# Xduino6_0.net
KiCad netlist of a schematic drawn in EAGLE
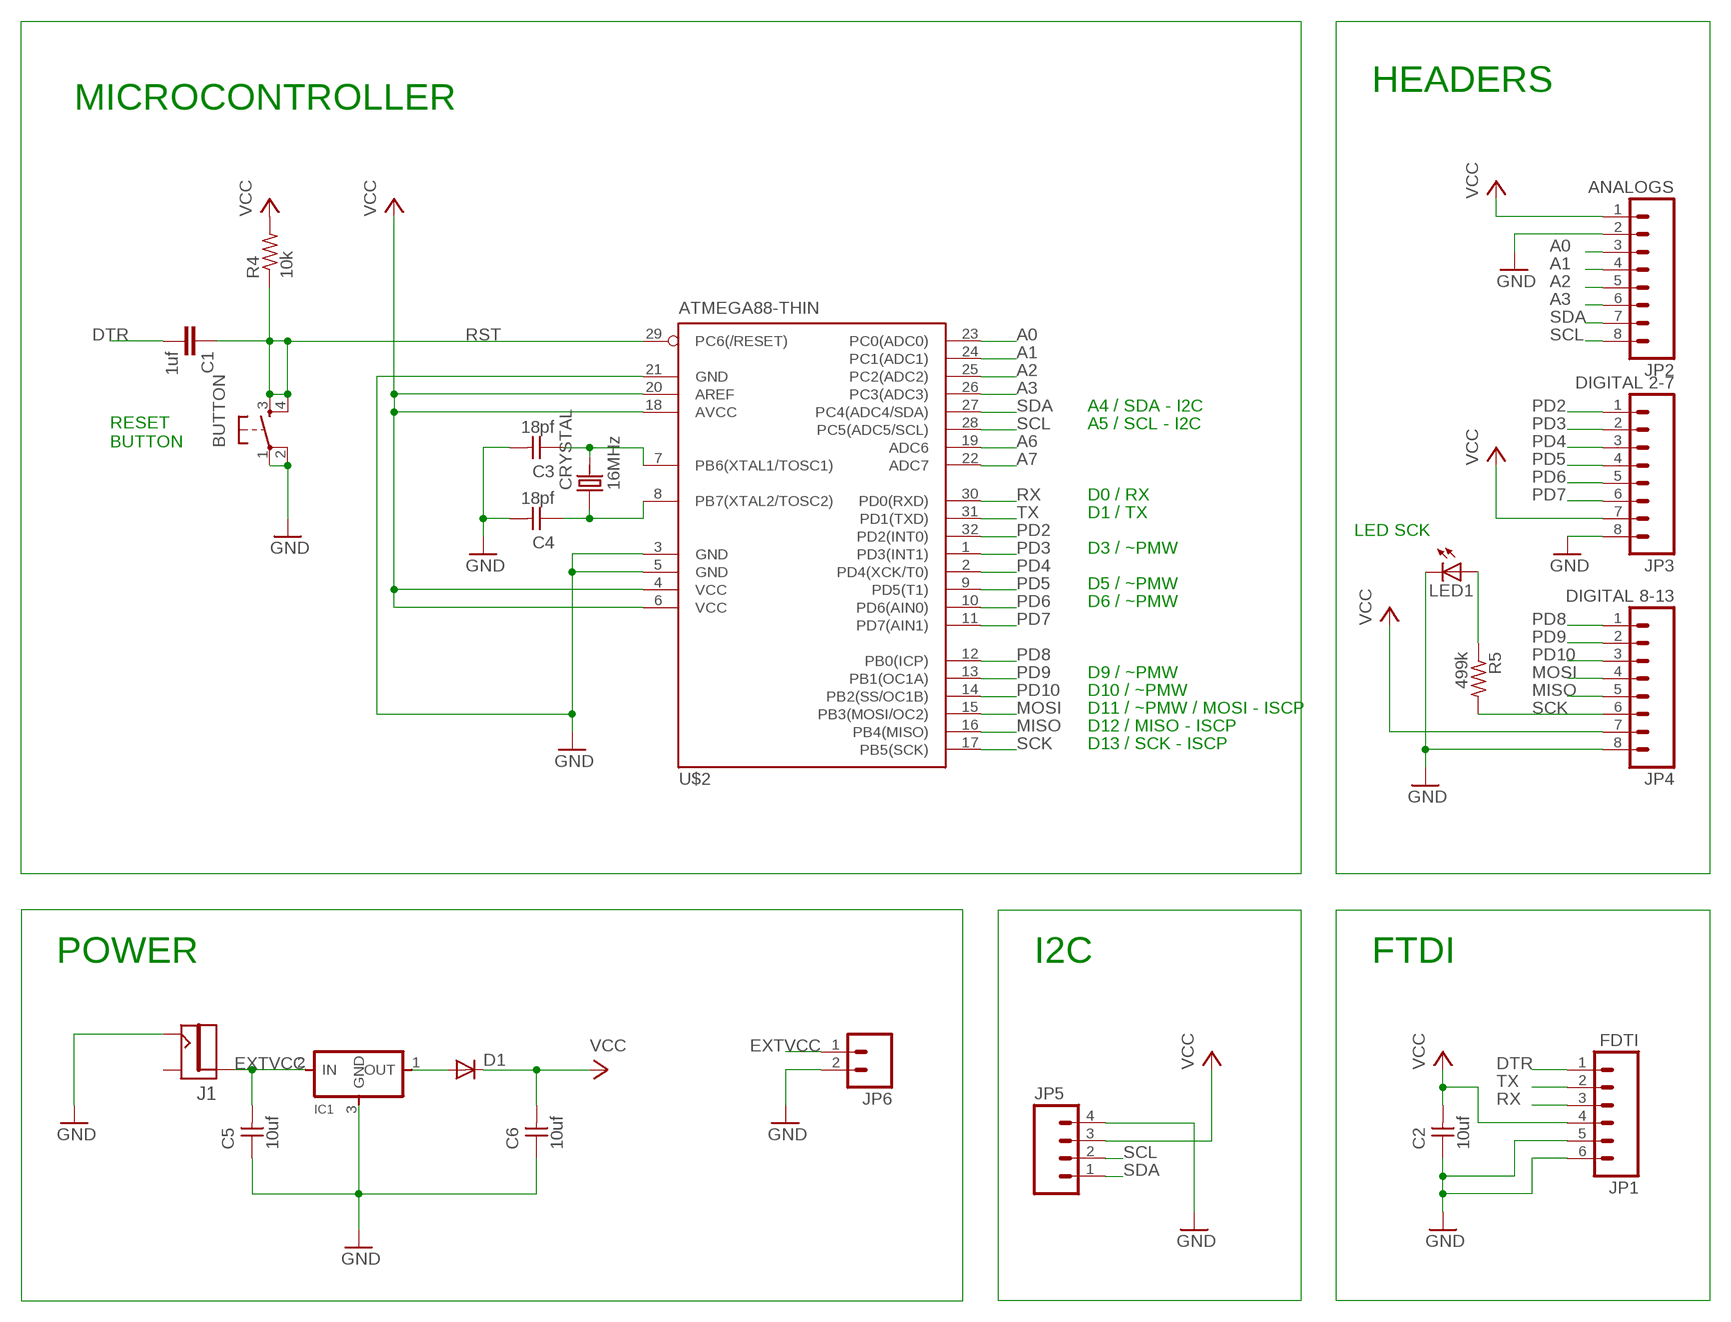
[diagram p0: schematic, sheet 1]

(export (version "E")
  (design (tool "Eeschema 10.0.6"))
  (components
    (comp (ref "BUTTON")
      (value "6MM_SWITCH6MM_SWITCH")
      (footprint "eagle-import:6MM_SWITCH")
      (libsource (lib "eagle-import") (part "6MM_SWITCH6MM_SWITCH"))
    )
    (comp (ref "C1")
      (value "1uf")
      (footprint "eagle-import:1206")
      (libsource (lib "eagle-import") (part "CAP1206"))
    )
    (comp (ref "C2")
      (value "10uf")
      (footprint "eagle-import:1206")
      (libsource (lib "eagle-import") (part "UNPOLARIZED_CAPACITOR1206"))
    )
    (comp (ref "C3")
      (value "18pf")
      (footprint "eagle-import:1206")
      (libsource (lib "eagle-import") (part "UNPOLARIZED_CAPACITOR1206"))
    )
    (comp (ref "C4")
      (value "18pf")
      (footprint "eagle-import:1206")
      (libsource (lib "eagle-import") (part "UNPOLARIZED_CAPACITOR1206"))
    )
    (comp (ref "C5")
      (value "10uf")
      (footprint "eagle-import:1206")
      (libsource (lib "eagle-import") (part "UNPOLARIZED_CAPACITOR1206"))
    )
    (comp (ref "C6")
      (value "10uf")
      (footprint "eagle-import:1206")
      (libsource (lib "eagle-import") (part "UNPOLARIZED_CAPACITOR1206"))
    )
    (comp (ref "CRYSTAL")
      (value "16MHz")
      (footprint "eagle-import:CS10")
      (libsource (lib "eagle-import") (part "CRYSTALCS10"))
    )
    (comp (ref "D1")
      (value "DIODESOD123")
      (footprint "eagle-import:SOD123")
      (libsource (lib "eagle-import") (part "DIODESOD123"))
    )
    (comp (ref "IC1")
      (value "REGULATORSOT23")
      (footprint "eagle-import:SOT23")
      (libsource (lib "eagle-import") (part "REGULATORSOT23"))
    )
    (comp (ref "J1")
      (value "JACK.65MM")
      (footprint "eagle-import:JACK_.65MM")
      (libsource (lib "eagle-import") (part "JACK.65MM"))
    )
    (comp (ref "JP1")
      (value "FDTI")
      (footprint "eagle-import:1X06-SMD_EDGE")
      (libsource (lib "eagle-import") (part "M061X06-SMD_EDGE_FEMALE"))
    )
    (comp (ref "JP2")
      (value "ANALOGS")
      (footprint "eagle-import:1X08")
      (libsource (lib "eagle-import") (part "M08"))
    )
    (comp (ref "JP3")
      (value "DIGITAL 2-7")
      (footprint "eagle-import:1X08")
      (libsource (lib "eagle-import") (part "M08"))
    )
    (comp (ref "JP4")
      (value "DIGITAL 8-13")
      (footprint "eagle-import:1X08")
      (libsource (lib "eagle-import") (part "M08"))
    )
    (comp (ref "JP5")
      (value "M04PTH")
      (footprint "eagle-import:1X04")
      (libsource (lib "eagle-import") (part "M04PTH"))
    )
    (comp (ref "JP6")
      (value "M02PTH")
      (footprint "eagle-import:1X02")
      (libsource (lib "eagle-import") (part "M02PTH"))
    )
    (comp (ref "LED1")
      (value "LED1206")
      (footprint "eagle-import:1206")
      (libsource (lib "eagle-import") (part "LED1206"))
    )
    (comp (ref "R4")
      (value "10k")
      (footprint "eagle-import:1206")
      (libsource (lib "eagle-import") (part "RESISTOR1206"))
    )
    (comp (ref "R5")
      (value "499k")
      (footprint "eagle-import:1206")
      (libsource (lib "eagle-import") (part "01_ng_RESISTOR1206"))
    )
    (comp (ref "U$2")
      (value "ATMEGA88-THIN")
      (footprint "eagle-import:TQFP32-08THIN")
      (libsource (lib "eagle-import") (part "ATMEGA88-THIN"))
    )
  )
  (nets
    (net (code "1") (name "/A0") (class "Default")
      (node (ref "JP2") (pin "3") (pinfunction "3_3") (pintype "passive"))
      (node (ref "U$2") (pin "23") (pinfunction "PC0(ADC0)_23") (pintype "bidirectional"))
    )
    (net (code "2") (name "/A1") (class "Default")
      (node (ref "JP2") (pin "4") (pinfunction "4_4") (pintype "passive"))
      (node (ref "U$2") (pin "24") (pinfunction "PC1(ADC1)_24") (pintype "bidirectional"))
    )
    (net (code "3") (name "/A2") (class "Default")
      (node (ref "JP2") (pin "5") (pinfunction "5_5") (pintype "passive"))
      (node (ref "U$2") (pin "25") (pinfunction "PC2(ADC2)_25") (pintype "bidirectional"))
    )
    (net (code "4") (name "/A3") (class "Default")
      (node (ref "JP2") (pin "6") (pinfunction "6_6") (pintype "passive"))
      (node (ref "U$2") (pin "26") (pinfunction "PC3(ADC3)_26") (pintype "bidirectional"))
    )
    (net (code "5") (name "/A6") (class "Default")
      (node (ref "U$2") (pin "19") (pinfunction "ADC6_19") (pintype "bidirectional"))
    )
    (net (code "6") (name "/A7") (class "Default")
      (node (ref "U$2") (pin "22") (pinfunction "ADC7_22") (pintype "bidirectional"))
    )
    (net (code "7") (name "/DTR") (class "Default")
      (node (ref "C1") (pin "2") (pinfunction "2_2") (pintype "passive"))
      (node (ref "JP1") (pin "1") (pinfunction "1_1") (pintype "passive"))
    )
    (net (code "8") (name "/EXTVCC") (class "Default")
      (node (ref "C5") (pin "2") (pinfunction "2_2") (pintype "passive"))
      (node (ref "IC1") (pin "2") (pinfunction "IN_2") (pintype "bidirectional"))
      (node (ref "J1") (pin "PIN") (pinfunction "PIN_PIN") (pintype "bidirectional"))
      (node (ref "JP6") (pin "1") (pinfunction "1_1") (pintype "passive"))
    )
    (net (code "9") (name "/MISO") (class "Default")
      (node (ref "JP4") (pin "5") (pinfunction "5_5") (pintype "passive"))
      (node (ref "U$2") (pin "16") (pinfunction "PB4(MISO)_16") (pintype "bidirectional"))
    )
    (net (code "10") (name "/MOSI") (class "Default")
      (node (ref "JP4") (pin "4") (pinfunction "4_4") (pintype "passive"))
      (node (ref "U$2") (pin "15") (pinfunction "PB3(MOSI/OC2)_15") (pintype "bidirectional"))
    )
    (net (code "11") (name "/PD2") (class "Default")
      (node (ref "JP3") (pin "1") (pinfunction "1_1") (pintype "passive"))
      (node (ref "U$2") (pin "32") (pinfunction "PD2(INT0)_32") (pintype "bidirectional"))
    )
    (net (code "12") (name "/PD3") (class "Default")
      (node (ref "JP3") (pin "2") (pinfunction "2_2") (pintype "passive"))
      (node (ref "U$2") (pin "1") (pinfunction "PD3(INT1)_1") (pintype "bidirectional"))
    )
    (net (code "13") (name "/PD4") (class "Default")
      (node (ref "JP3") (pin "3") (pinfunction "3_3") (pintype "passive"))
      (node (ref "U$2") (pin "2") (pinfunction "PD4(XCK/T0)_2") (pintype "bidirectional"))
    )
    (net (code "14") (name "/PD5") (class "Default")
      (node (ref "JP3") (pin "4") (pinfunction "4_4") (pintype "passive"))
      (node (ref "U$2") (pin "9") (pinfunction "PD5(T1)_9") (pintype "bidirectional"))
    )
    (net (code "15") (name "/PD6") (class "Default")
      (node (ref "JP3") (pin "5") (pinfunction "5_5") (pintype "passive"))
      (node (ref "U$2") (pin "10") (pinfunction "PD6(AIN0)_10") (pintype "bidirectional"))
    )
    (net (code "16") (name "/PD7") (class "Default")
      (node (ref "JP3") (pin "6") (pinfunction "6_6") (pintype "passive"))
      (node (ref "U$2") (pin "11") (pinfunction "PD7(AIN1)_11") (pintype "bidirectional"))
    )
    (net (code "17") (name "/PD8") (class "Default")
      (node (ref "JP4") (pin "1") (pinfunction "1_1") (pintype "passive"))
      (node (ref "U$2") (pin "12") (pinfunction "PB0(ICP)_12") (pintype "bidirectional"))
    )
    (net (code "18") (name "/PD9") (class "Default")
      (node (ref "JP4") (pin "2") (pinfunction "2_2") (pintype "passive"))
      (node (ref "U$2") (pin "13") (pinfunction "PB1(OC1A)_13") (pintype "bidirectional"))
    )
    (net (code "19") (name "/PD10") (class "Default")
      (node (ref "JP4") (pin "3") (pinfunction "3_3") (pintype "passive"))
      (node (ref "U$2") (pin "14") (pinfunction "PB2(SS/OC1B)_14") (pintype "bidirectional"))
    )
    (net (code "20") (name "/RST") (class "Default")
      (node (ref "BUTTON") (pin "3") (pinfunction "S_3") (pintype "passive"))
      (node (ref "BUTTON") (pin "4") (pinfunction "S1_4") (pintype "passive"))
      (node (ref "C1") (pin "1") (pinfunction "1_1") (pintype "passive"))
      (node (ref "R4") (pin "1") (pinfunction "1_1") (pintype "passive"))
      (node (ref "U$2") (pin "29") (pinfunction "PC6(/RESET)_29") (pintype "bidirectional"))
    )
    (net (code "21") (name "/RX") (class "Default")
      (node (ref "JP1") (pin "3") (pinfunction "3_3") (pintype "passive"))
      (node (ref "U$2") (pin "30") (pinfunction "PD0(RXD)_30") (pintype "bidirectional"))
    )
    (net (code "22") (name "/SCK") (class "Default")
      (node (ref "JP4") (pin "6") (pinfunction "6_6") (pintype "passive"))
      (node (ref "R5") (pin "2") (pinfunction "2_2") (pintype "passive"))
      (node (ref "U$2") (pin "17") (pinfunction "PB5(SCK)_17") (pintype "bidirectional"))
    )
    (net (code "23") (name "/SCL") (class "Default")
      (node (ref "JP2") (pin "8") (pinfunction "8_8") (pintype "passive"))
      (node (ref "JP5") (pin "2") (pinfunction "2_2") (pintype "passive"))
      (node (ref "U$2") (pin "28") (pinfunction "PC5(ADC5/SCL)_28") (pintype "bidirectional"))
    )
    (net (code "24") (name "/SDA") (class "Default")
      (node (ref "JP2") (pin "7") (pinfunction "7_7") (pintype "passive"))
      (node (ref "JP5") (pin "1") (pinfunction "1_1") (pintype "passive"))
      (node (ref "U$2") (pin "27") (pinfunction "PC4(ADC4/SDA)_27") (pintype "bidirectional"))
    )
    (net (code "25") (name "/TX") (class "Default")
      (node (ref "JP1") (pin "2") (pinfunction "2_2") (pintype "passive"))
      (node (ref "U$2") (pin "31") (pinfunction "PD1(TXD)_31") (pintype "bidirectional"))
    )
    (net (code "26") (name "GND") (class "Default")
      (node (ref "BUTTON") (pin "1") (pinfunction "P_1") (pintype "passive"))
      (node (ref "BUTTON") (pin "2") (pinfunction "P1_2") (pintype "passive"))
      (node (ref "C2") (pin "1") (pinfunction "1_1") (pintype "passive"))
      (node (ref "C3") (pin "2") (pinfunction "2_2") (pintype "passive"))
      (node (ref "C4") (pin "2") (pinfunction "2_2") (pintype "passive"))
      (node (ref "C5") (pin "1") (pinfunction "1_1") (pintype "passive"))
      (node (ref "C6") (pin "1") (pinfunction "1_1") (pintype "passive"))
      (node (ref "IC1") (pin "3") (pinfunction "GND_3") (pintype "bidirectional"))
      (node (ref "J1") (pin "SHUNT") (pinfunction "CONTACT_SHUNT") (pintype "bidirectional"))
      (node (ref "JP1") (pin "5") (pinfunction "5_5") (pintype "passive"))
      (node (ref "JP1") (pin "6") (pinfunction "6_6") (pintype "passive"))
      (node (ref "JP2") (pin "2") (pinfunction "2_2") (pintype "passive"))
      (node (ref "JP3") (pin "8") (pinfunction "8_8") (pintype "passive"))
      (node (ref "JP4") (pin "8") (pinfunction "8_8") (pintype "passive"))
      (node (ref "JP5") (pin "4") (pinfunction "4_4") (pintype "passive"))
      (node (ref "JP6") (pin "2") (pinfunction "2_2") (pintype "passive"))
      (node (ref "LED1") (pin "2") (pinfunction "C_2") (pintype "passive"))
      (node (ref "U$2") (pin "21") (pinfunction "GND_21") (pintype "power_in"))
      (node (ref "U$2") (pin "3") (pinfunction "GND_3") (pintype "power_in"))
      (node (ref "U$2") (pin "5") (pinfunction "GND_5") (pintype "power_in"))
    )
    (net (code "27") (name "Net-(CRYSTAL-1)") (class "Default")
      (node (ref "C4") (pin "1") (pinfunction "1_1") (pintype "passive"))
      (node (ref "CRYSTAL") (pin "P$1") (pinfunction "1_P$1") (pintype "passive"))
      (node (ref "U$2") (pin "8") (pinfunction "PB7(XTAL2/TOSC2)_8") (pintype "bidirectional"))
    )
    (net (code "28") (name "Net-(CRYSTAL-2)") (class "Default")
      (node (ref "C3") (pin "1") (pinfunction "1_1") (pintype "passive"))
      (node (ref "CRYSTAL") (pin "P$2") (pinfunction "2_P$2") (pintype "passive"))
      (node (ref "U$2") (pin "7") (pinfunction "PB6(XTAL1/TOSC1)_7") (pintype "bidirectional"))
    )
    (net (code "29") (name "Net-(D1-A)") (class "Default")
      (node (ref "D1") (pin "ANODE") (pinfunction "A_ANODE") (pintype "passive"))
      (node (ref "IC1") (pin "1") (pinfunction "OUT_1") (pintype "bidirectional"))
    )
    (net (code "30") (name "Net-(LED1-A)") (class "Default")
      (node (ref "LED1") (pin "1") (pinfunction "A_1") (pintype "passive"))
      (node (ref "R5") (pin "1") (pinfunction "1_1") (pintype "passive"))
    )
    (net (code "31") (name "VCC") (class "Default")
      (node (ref "C2") (pin "2") (pinfunction "2_2") (pintype "passive"))
      (node (ref "C6") (pin "2") (pinfunction "2_2") (pintype "passive"))
      (node (ref "D1") (pin "CATHODE") (pinfunction "C_CATHODE") (pintype "passive"))
      (node (ref "JP1") (pin "4") (pinfunction "4_4") (pintype "passive"))
      (node (ref "JP2") (pin "1") (pinfunction "1_1") (pintype "passive"))
      (node (ref "JP3") (pin "7") (pinfunction "7_7") (pintype "passive"))
      (node (ref "JP4") (pin "7") (pinfunction "7_7") (pintype "passive"))
      (node (ref "JP5") (pin "3") (pinfunction "3_3") (pintype "passive"))
      (node (ref "R4") (pin "2") (pinfunction "2_2") (pintype "passive"))
      (node (ref "U$2") (pin "18") (pinfunction "AVCC_18") (pintype "power_in"))
      (node (ref "U$2") (pin "20") (pinfunction "AREF_20") (pintype "passive"))
      (node (ref "U$2") (pin "4") (pinfunction "VCC_4") (pintype "power_in"))
      (node (ref "U$2") (pin "6") (pinfunction "VCC_6") (pintype "power_in"))
    )
    (net (code "32") (name "unconnected-(J1-SHUNT-PadCONTACT)") (class "Default")
      (node (ref "J1") (pin "CONTACT") (pinfunction "SHUNT_CONTACT") (pintype "bidirectional"))
    )
  )
)
